# W65C22N6TPLG-14_to_DIP_VIA_6522_Adapter.net
KiCad netlist of a schematic drawn in Altium Designer
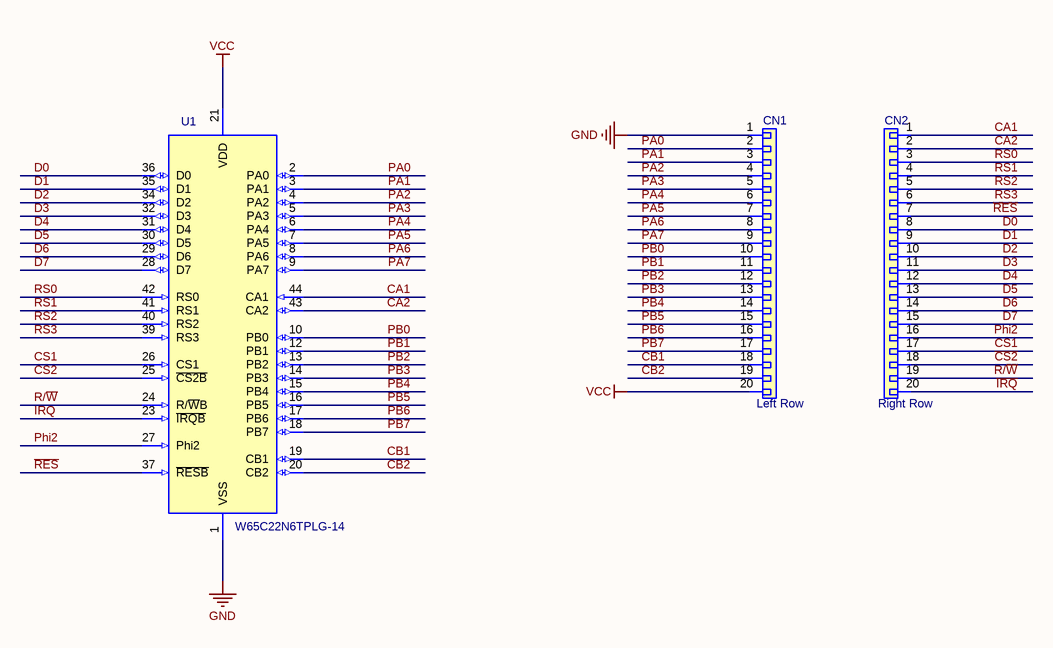
[diagram p0: W65C22N6TPLG-14 to DIP VIA 6522 Adapter.SchDoc]

(export (version "E")
  (design (tool "Eeschema 10.0.6"))
  (components
    (comp (ref "CN1")
      (value "Left Row")
      (footprint "Pin Header 01x20 2.54mm precision Horizontal Male")
      (description "Conn Header Vert 20POS 2MM")
      (libsource (lib "PCB-Tech Cloud") (part "CONN 01x20"))
    )
    (comp (ref "CN2")
      (value "Right Row")
      (footprint "Pin Header 01x20 2.54mm precision Horizontal Male")
      (description "Conn Header Vert 20POS 2MM")
      (libsource (lib "") (part "CONN 01x20_1"))
    )
    (comp (ref "U1")
      (value "W65C22N6TPLG-14")
      (footprint "W65C22N6TPLG-14 with PLCC Socket")
      (description "I/O Controller Interface IC Versatile Interface Adapter")
      (libsource (lib "PCB-Tech Cloud") (part "W65C22N6TPLG-14"))
    )
  )
  (nets
    (net (code "1") (name "/CA1") (class "Default")
      (node (ref "CN2") (pin "1") (pinfunction "1_1") (pintype "passive"))
      (node (ref "U1") (pin "44") (pinfunction "CA1_44") (pintype "input"))
    )
    (net (code "2") (name "/CA2") (class "Default")
      (node (ref "CN2") (pin "2") (pinfunction "2_2") (pintype "passive"))
      (node (ref "U1") (pin "43") (pinfunction "CA2_43") (pintype "bidirectional"))
    )
    (net (code "3") (name "/CB1") (class "Default")
      (node (ref "CN1") (pin "18") (pinfunction "18_18") (pintype "passive"))
      (node (ref "U1") (pin "19") (pinfunction "CB1_19") (pintype "bidirectional"))
    )
    (net (code "4") (name "/CB2") (class "Default")
      (node (ref "CN1") (pin "19") (pinfunction "19_19") (pintype "passive"))
      (node (ref "U1") (pin "20") (pinfunction "CB2_20") (pintype "bidirectional"))
    )
    (net (code "5") (name "/CS1") (class "Default")
      (node (ref "CN2") (pin "17") (pinfunction "17_17") (pintype "passive"))
      (node (ref "U1") (pin "26") (pinfunction "CS1_26") (pintype "input"))
    )
    (net (code "6") (name "/D0") (class "Default")
      (node (ref "CN2") (pin "8") (pinfunction "8_8") (pintype "passive"))
      (node (ref "U1") (pin "36") (pinfunction "D0_36") (pintype "bidirectional"))
    )
    (net (code "7") (name "/D1") (class "Default")
      (node (ref "CN2") (pin "9") (pinfunction "9_9") (pintype "passive"))
      (node (ref "U1") (pin "35") (pinfunction "D1_35") (pintype "bidirectional"))
    )
    (net (code "8") (name "/D2") (class "Default")
      (node (ref "CN2") (pin "10") (pinfunction "10_10") (pintype "passive"))
      (node (ref "U1") (pin "34") (pinfunction "D2_34") (pintype "bidirectional"))
    )
    (net (code "9") (name "/D3") (class "Default")
      (node (ref "CN2") (pin "11") (pinfunction "11_11") (pintype "passive"))
      (node (ref "U1") (pin "32") (pinfunction "D3_32") (pintype "bidirectional"))
    )
    (net (code "10") (name "/D4") (class "Default")
      (node (ref "CN2") (pin "12") (pinfunction "12_12") (pintype "passive"))
      (node (ref "U1") (pin "31") (pinfunction "D4_31") (pintype "bidirectional"))
    )
    (net (code "11") (name "/D5") (class "Default")
      (node (ref "CN2") (pin "13") (pinfunction "13_13") (pintype "passive"))
      (node (ref "U1") (pin "30") (pinfunction "D5_30") (pintype "bidirectional"))
    )
    (net (code "12") (name "/D6") (class "Default")
      (node (ref "CN2") (pin "14") (pinfunction "14_14") (pintype "passive"))
      (node (ref "U1") (pin "29") (pinfunction "D6_29") (pintype "bidirectional"))
    )
    (net (code "13") (name "/D7") (class "Default")
      (node (ref "CN2") (pin "15") (pinfunction "15_15") (pintype "passive"))
      (node (ref "U1") (pin "28") (pinfunction "D7_28") (pintype "bidirectional"))
    )
    (net (code "14") (name "/PA0") (class "Default")
      (node (ref "CN1") (pin "2") (pinfunction "2_2") (pintype "passive"))
      (node (ref "U1") (pin "2") (pinfunction "PA0_2") (pintype "bidirectional"))
    )
    (net (code "15") (name "/PA1") (class "Default")
      (node (ref "CN1") (pin "3") (pinfunction "3_3") (pintype "passive"))
      (node (ref "U1") (pin "3") (pinfunction "PA1_3") (pintype "bidirectional"))
    )
    (net (code "16") (name "/PA2") (class "Default")
      (node (ref "CN1") (pin "4") (pinfunction "4_4") (pintype "passive"))
      (node (ref "U1") (pin "4") (pinfunction "PA2_4") (pintype "bidirectional"))
    )
    (net (code "17") (name "/PA3") (class "Default")
      (node (ref "CN1") (pin "5") (pinfunction "5_5") (pintype "passive"))
      (node (ref "U1") (pin "5") (pinfunction "PA3_5") (pintype "bidirectional"))
    )
    (net (code "18") (name "/PA4") (class "Default")
      (node (ref "CN1") (pin "6") (pinfunction "6_6") (pintype "passive"))
      (node (ref "U1") (pin "6") (pinfunction "PA4_6") (pintype "bidirectional"))
    )
    (net (code "19") (name "/PA5") (class "Default")
      (node (ref "CN1") (pin "7") (pinfunction "7_7") (pintype "passive"))
      (node (ref "U1") (pin "7") (pinfunction "PA5_7") (pintype "bidirectional"))
    )
    (net (code "20") (name "/PA6") (class "Default")
      (node (ref "CN1") (pin "8") (pinfunction "8_8") (pintype "passive"))
      (node (ref "U1") (pin "8") (pinfunction "PA6_8") (pintype "bidirectional"))
    )
    (net (code "21") (name "/PA7") (class "Default")
      (node (ref "CN1") (pin "9") (pinfunction "9_9") (pintype "passive"))
      (node (ref "U1") (pin "9") (pinfunction "PA7_9") (pintype "bidirectional"))
    )
    (net (code "22") (name "/PB0") (class "Default")
      (node (ref "CN1") (pin "10") (pinfunction "10_10") (pintype "passive"))
      (node (ref "U1") (pin "10") (pinfunction "PB0_10") (pintype "bidirectional"))
    )
    (net (code "23") (name "/PB1") (class "Default")
      (node (ref "CN1") (pin "11") (pinfunction "11_11") (pintype "passive"))
      (node (ref "U1") (pin "12") (pinfunction "PB1_12") (pintype "bidirectional"))
    )
    (net (code "24") (name "/PB2") (class "Default")
      (node (ref "CN1") (pin "12") (pinfunction "12_12") (pintype "passive"))
      (node (ref "U1") (pin "13") (pinfunction "PB2_13") (pintype "bidirectional"))
    )
    (net (code "25") (name "/PB3") (class "Default")
      (node (ref "CN1") (pin "13") (pinfunction "13_13") (pintype "passive"))
      (node (ref "U1") (pin "14") (pinfunction "PB3_14") (pintype "bidirectional"))
    )
    (net (code "26") (name "/PB4") (class "Default")
      (node (ref "CN1") (pin "14") (pinfunction "14_14") (pintype "passive"))
      (node (ref "U1") (pin "15") (pinfunction "PB4_15") (pintype "bidirectional"))
    )
    (net (code "27") (name "/PB5") (class "Default")
      (node (ref "CN1") (pin "15") (pinfunction "15_15") (pintype "passive"))
      (node (ref "U1") (pin "16") (pinfunction "PB5_16") (pintype "bidirectional"))
    )
    (net (code "28") (name "/PB6") (class "Default")
      (node (ref "CN1") (pin "16") (pinfunction "16_16") (pintype "passive"))
      (node (ref "U1") (pin "17") (pinfunction "PB6_17") (pintype "bidirectional"))
    )
    (net (code "29") (name "/PB7") (class "Default")
      (node (ref "CN1") (pin "17") (pinfunction "17_17") (pintype "passive"))
      (node (ref "U1") (pin "18") (pinfunction "PB7_18") (pintype "bidirectional"))
    )
    (net (code "30") (name "/Phi2") (class "Default")
      (node (ref "CN2") (pin "16") (pinfunction "16_16") (pintype "passive"))
      (node (ref "U1") (pin "27") (pinfunction "Phi2_27") (pintype "input"))
    )
    (net (code "31") (name "/RS0") (class "Default")
      (node (ref "CN2") (pin "3") (pinfunction "3_3") (pintype "passive"))
      (node (ref "U1") (pin "42") (pinfunction "RS0_42") (pintype "input"))
    )
    (net (code "32") (name "/RS1") (class "Default")
      (node (ref "CN2") (pin "4") (pinfunction "4_4") (pintype "passive"))
      (node (ref "U1") (pin "41") (pinfunction "RS1_41") (pintype "input"))
    )
    (net (code "33") (name "/RS2") (class "Default")
      (node (ref "CN2") (pin "5") (pinfunction "5_5") (pintype "passive"))
      (node (ref "U1") (pin "40") (pinfunction "RS2_40") (pintype "input"))
    )
    (net (code "34") (name "/RS3") (class "Default")
      (node (ref "CN2") (pin "6") (pinfunction "6_6") (pintype "passive"))
      (node (ref "U1") (pin "39") (pinfunction "RS3_39") (pintype "input"))
    )
    (net (code "35") (name "/R{slash}~{W}") (class "Default")
      (node (ref "CN2") (pin "19") (pinfunction "19_19") (pintype "passive"))
      (node (ref "U1") (pin "24") (pinfunction "R/~{W}B_24") (pintype "input"))
    )
    (net (code "36") (name "/~{CS2}") (class "Default")
      (node (ref "CN2") (pin "18") (pinfunction "18_18") (pintype "passive"))
      (node (ref "U1") (pin "25") (pinfunction "~{CS2B}_25") (pintype "input"))
    )
    (net (code "37") (name "/~{IRQ}") (class "Default")
      (node (ref "CN2") (pin "20") (pinfunction "20_20") (pintype "passive"))
      (node (ref "U1") (pin "23") (pinfunction "~{IRQB}_23") (pintype "input"))
    )
    (net (code "38") (name "/~{RES}") (class "Default")
      (node (ref "CN2") (pin "7") (pinfunction "7_7") (pintype "passive"))
      (node (ref "U1") (pin "37") (pinfunction "~{RESB}_37") (pintype "input"))
    )
    (net (code "39") (name "GND") (class "Default")
      (node (ref "CN1") (pin "1") (pinfunction "1_1") (pintype "passive"))
      (node (ref "U1") (pin "1") (pinfunction "VSS_1") (pintype "power_in"))
    )
    (net (code "40") (name "VCC") (class "Default")
      (node (ref "CN1") (pin "20") (pinfunction "20_20") (pintype "passive"))
      (node (ref "U1") (pin "21") (pinfunction "VDD_21") (pintype "power_in"))
    )
    (net (code "41") (name "unconnected-(U1-NC-Pad11)") (class "Default")
      (node (ref "U1") (pin "11") (pinfunction "NC_11") (pintype "passive"))
    )
    (net (code "42") (name "unconnected-(U1-NC-Pad22)") (class "Default")
      (node (ref "U1") (pin "22") (pinfunction "NC_22") (pintype "passive"))
    )
    (net (code "43") (name "unconnected-(U1-NC-Pad33)") (class "Default")
      (node (ref "U1") (pin "33") (pinfunction "NC_33") (pintype "passive"))
    )
    (net (code "44") (name "unconnected-(U1-NC-Pad38)") (class "Default")
      (node (ref "U1") (pin "38") (pinfunction "NC_38") (pintype "passive"))
    )
  )
)
